# timing.net
KiCad netlist of a schematic drawn in Altium Designer
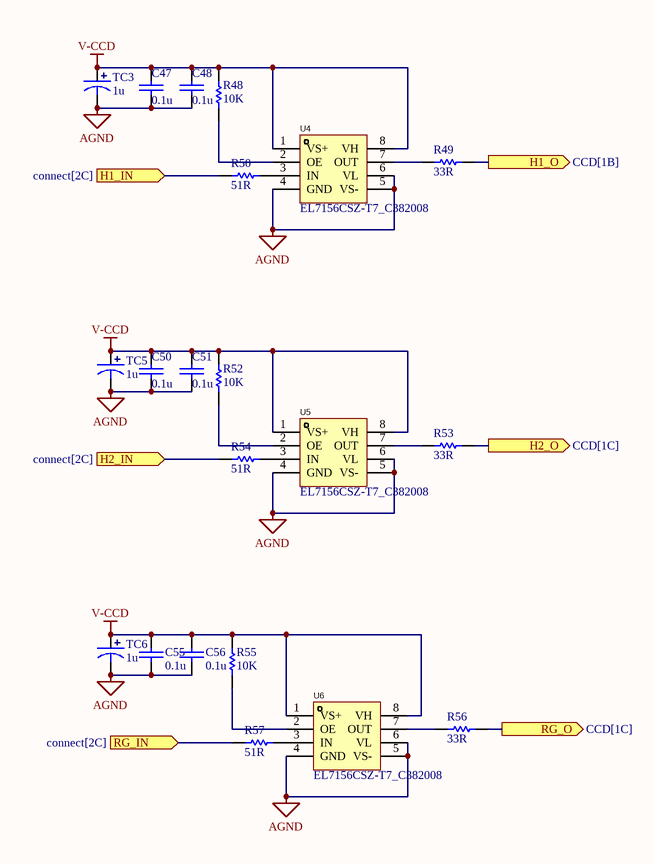
[diagram p0: timing.SchDoc]

(export (version "E")
  (design (tool "Eeschema 10.0.6"))
  (components
    (comp (ref "C47")
      (value "0.1u")
      (footprint "0603C")
      (description "无极性电容")
      (libsource (lib "1.00-阻容感") (part "CAP"))
    )
    (comp (ref "C48")
      (value "0.1u")
      (footprint "0603C")
      (description "无极性电容")
      (libsource (lib "1.00-阻容感") (part "CAP"))
    )
    (comp (ref "C50")
      (value "0.1u")
      (footprint "0603C")
      (description "无极性电容")
      (libsource (lib "1.00-阻容感") (part "CAP"))
    )
    (comp (ref "C51")
      (value "0.1u")
      (footprint "0603C")
      (description "无极性电容")
      (libsource (lib "1.00-阻容感") (part "CAP"))
    )
    (comp (ref "C55")
      (value "0.1u")
      (footprint "0603C")
      (description "无极性电容")
      (libsource (lib "1.00-阻容感") (part "CAP"))
    )
    (comp (ref "C56")
      (value "0.1u")
      (footprint "0603C")
      (description "无极性电容")
      (libsource (lib "1.00-阻容感") (part "CAP"))
    )
    (comp (ref "R48")
      (value "10K")
      (footprint "0603R")
      (description "电阻")
      (libsource (lib "1.00-阻容感") (part "RES"))
    )
    (comp (ref "R49")
      (value "33R")
      (footprint "0603R")
      (description "电阻")
      (libsource (lib "1.00-阻容感") (part "RES"))
    )
    (comp (ref "R50")
      (value "51R")
      (footprint "0603R")
      (description "电阻")
      (libsource (lib "1.00-阻容感") (part "RES"))
    )
    (comp (ref "R52")
      (value "10K")
      (footprint "0603R")
      (description "电阻")
      (libsource (lib "1.00-阻容感") (part "RES"))
    )
    (comp (ref "R53")
      (value "33R")
      (footprint "0603R")
      (description "电阻")
      (libsource (lib "1.00-阻容感") (part "RES"))
    )
    (comp (ref "R54")
      (value "51R")
      (footprint "0603R")
      (description "电阻")
      (libsource (lib "1.00-阻容感") (part "RES"))
    )
    (comp (ref "R55")
      (value "10K")
      (footprint "0603R")
      (description "电阻")
      (libsource (lib "1.00-阻容感") (part "RES"))
    )
    (comp (ref "R56")
      (value "33R")
      (footprint "0603R")
      (description "电阻")
      (libsource (lib "1.00-阻容感") (part "RES"))
    )
    (comp (ref "R57")
      (value "51R")
      (footprint "0603R")
      (description "电阻")
      (libsource (lib "1.00-阻容感") (part "RES"))
    )
    (comp (ref "TC3")
      (value "1u")
      (footprint "TAJ-A/3216")
      (description "钽电容")
      (libsource (lib "1.00-阻容感") (part "TCAP"))
    )
    (comp (ref "TC5")
      (value "1u")
      (footprint "TAJ-A/3216")
      (description "钽电容")
      (libsource (lib "1.00-阻容感") (part "TCAP"))
    )
    (comp (ref "TC6")
      (value "1u")
      (footprint "TAJ-A/3216")
      (description "钽电容")
      (libsource (lib "1.00-阻容感") (part "TCAP"))
    )
    (comp (ref "U4")
      (value "EL7156CSZ-T7_C382008")
      (footprint "SOIC-8")
      (description "栅极驱动器")
      (fields
        (field (name "MANUFACTURER") "Intersil(英特矽尔)")
        (field (name "MANUFACTURER PART") "EL7156CSZ-T7")
      )
      (libsource (lib "0.05-mylib") (part "EL7156CSZ-T7"))
    )
    (comp (ref "U5")
      (value "EL7156CSZ-T7_C382008")
      (footprint "SOIC-8")
      (description "栅极驱动器")
      (fields
        (field (name "MANUFACTURER") "Intersil(英特矽尔)")
        (field (name "MANUFACTURER PART") "EL7156CSZ-T7")
      )
      (libsource (lib "0.05-mylib") (part "EL7156CSZ-T7"))
    )
    (comp (ref "U6")
      (value "EL7156CSZ-T7_C382008")
      (footprint "SOIC-8")
      (description "栅极驱动器")
      (fields
        (field (name "MANUFACTURER") "Intersil(英特矽尔)")
        (field (name "MANUFACTURER PART") "EL7156CSZ-T7")
      )
      (libsource (lib "0.05-mylib") (part "EL7156CSZ-T7"))
    )
  )
  (nets
    (net (code "1") (name "/H1_IN") (class "Default")
      (node (ref "R50") (pin "2") (pinfunction "2_2") (pintype "passive"))
    )
    (net (code "2") (name "/H1_O") (class "Default")
      (node (ref "R49") (pin "1") (pinfunction "1_1") (pintype "passive"))
    )
    (net (code "3") (name "/H2_IN") (class "Default")
      (node (ref "R54") (pin "2") (pinfunction "2_2") (pintype "passive"))
    )
    (net (code "4") (name "/H2_O") (class "Default")
      (node (ref "R53") (pin "1") (pinfunction "1_1") (pintype "passive"))
    )
    (net (code "5") (name "/RG_IN") (class "Default")
      (node (ref "R57") (pin "2") (pinfunction "2_2") (pintype "passive"))
    )
    (net (code "6") (name "/RG_O") (class "Default")
      (node (ref "R56") (pin "1") (pinfunction "1_1") (pintype "passive"))
    )
    (net (code "7") (name "AGND") (class "Default")
      (node (ref "C47") (pin "2") (pinfunction "2_2") (pintype "passive"))
      (node (ref "C48") (pin "2") (pinfunction "2_2") (pintype "passive"))
      (node (ref "C50") (pin "2") (pinfunction "2_2") (pintype "passive"))
      (node (ref "C51") (pin "2") (pinfunction "2_2") (pintype "passive"))
      (node (ref "C55") (pin "2") (pinfunction "2_2") (pintype "passive"))
      (node (ref "C56") (pin "2") (pinfunction "2_2") (pintype "passive"))
      (node (ref "TC3") (pin "2") (pinfunction "2_2") (pintype "passive"))
      (node (ref "TC5") (pin "2") (pinfunction "2_2") (pintype "passive"))
      (node (ref "TC6") (pin "2") (pinfunction "2_2") (pintype "passive"))
      (node (ref "U4") (pin "4") (pinfunction "GND_4") (pintype "passive"))
      (node (ref "U4") (pin "5") (pinfunction "VS-_5") (pintype "passive"))
      (node (ref "U4") (pin "6") (pinfunction "VL_6") (pintype "passive"))
      (node (ref "U5") (pin "4") (pinfunction "GND_4") (pintype "passive"))
      (node (ref "U5") (pin "5") (pinfunction "VS-_5") (pintype "passive"))
      (node (ref "U5") (pin "6") (pinfunction "VL_6") (pintype "passive"))
      (node (ref "U6") (pin "4") (pinfunction "GND_4") (pintype "passive"))
      (node (ref "U6") (pin "5") (pinfunction "VS-_5") (pintype "passive"))
      (node (ref "U6") (pin "6") (pinfunction "VL_6") (pintype "passive"))
    )
    (net (code "8") (name "Net-(U4-IN)") (class "Default")
      (node (ref "R50") (pin "1") (pinfunction "1_1") (pintype "passive"))
      (node (ref "U4") (pin "3") (pinfunction "IN_3") (pintype "passive"))
    )
    (net (code "9") (name "Net-(U4-OE)") (class "Default")
      (node (ref "R48") (pin "2") (pinfunction "2_2") (pintype "passive"))
      (node (ref "U4") (pin "2") (pinfunction "OE_2") (pintype "passive"))
    )
    (net (code "10") (name "Net-(U4-OUT)") (class "Default")
      (node (ref "R49") (pin "2") (pinfunction "2_2") (pintype "passive"))
      (node (ref "U4") (pin "7") (pinfunction "OUT_7") (pintype "passive"))
    )
    (net (code "11") (name "Net-(U5-IN)") (class "Default")
      (node (ref "R54") (pin "1") (pinfunction "1_1") (pintype "passive"))
      (node (ref "U5") (pin "3") (pinfunction "IN_3") (pintype "passive"))
    )
    (net (code "12") (name "Net-(U5-OE)") (class "Default")
      (node (ref "R52") (pin "2") (pinfunction "2_2") (pintype "passive"))
      (node (ref "U5") (pin "2") (pinfunction "OE_2") (pintype "passive"))
    )
    (net (code "13") (name "Net-(U5-OUT)") (class "Default")
      (node (ref "R53") (pin "2") (pinfunction "2_2") (pintype "passive"))
      (node (ref "U5") (pin "7") (pinfunction "OUT_7") (pintype "passive"))
    )
    (net (code "14") (name "Net-(U6-IN)") (class "Default")
      (node (ref "R57") (pin "1") (pinfunction "1_1") (pintype "passive"))
      (node (ref "U6") (pin "3") (pinfunction "IN_3") (pintype "passive"))
    )
    (net (code "15") (name "Net-(U6-OE)") (class "Default")
      (node (ref "R55") (pin "2") (pinfunction "2_2") (pintype "passive"))
      (node (ref "U6") (pin "2") (pinfunction "OE_2") (pintype "passive"))
    )
    (net (code "16") (name "Net-(U6-OUT)") (class "Default")
      (node (ref "R56") (pin "2") (pinfunction "2_2") (pintype "passive"))
      (node (ref "U6") (pin "7") (pinfunction "OUT_7") (pintype "passive"))
    )
    (net (code "17") (name "V-CCD") (class "Default")
      (node (ref "C47") (pin "1") (pinfunction "1_1") (pintype "passive"))
      (node (ref "C48") (pin "1") (pinfunction "1_1") (pintype "passive"))
      (node (ref "C50") (pin "1") (pinfunction "1_1") (pintype "passive"))
      (node (ref "C51") (pin "1") (pinfunction "1_1") (pintype "passive"))
      (node (ref "C55") (pin "1") (pinfunction "1_1") (pintype "passive"))
      (node (ref "C56") (pin "1") (pinfunction "1_1") (pintype "passive"))
      (node (ref "R48") (pin "1") (pinfunction "1_1") (pintype "passive"))
      (node (ref "R52") (pin "1") (pinfunction "1_1") (pintype "passive"))
      (node (ref "R55") (pin "1") (pinfunction "1_1") (pintype "passive"))
      (node (ref "TC3") (pin "1") (pinfunction "1_1") (pintype "passive"))
      (node (ref "TC5") (pin "1") (pinfunction "1_1") (pintype "passive"))
      (node (ref "TC6") (pin "1") (pinfunction "1_1") (pintype "passive"))
      (node (ref "U4") (pin "1") (pinfunction "VS+_1") (pintype "passive"))
      (node (ref "U4") (pin "8") (pinfunction "VH_8") (pintype "passive"))
      (node (ref "U5") (pin "1") (pinfunction "VS+_1") (pintype "passive"))
      (node (ref "U5") (pin "8") (pinfunction "VH_8") (pintype "passive"))
      (node (ref "U6") (pin "1") (pinfunction "VS+_1") (pintype "passive"))
      (node (ref "U6") (pin "8") (pinfunction "VH_8") (pintype "passive"))
    )
  )
)
